# LinearVCA.net
KiCad netlist of a schematic drawn in EAGLE
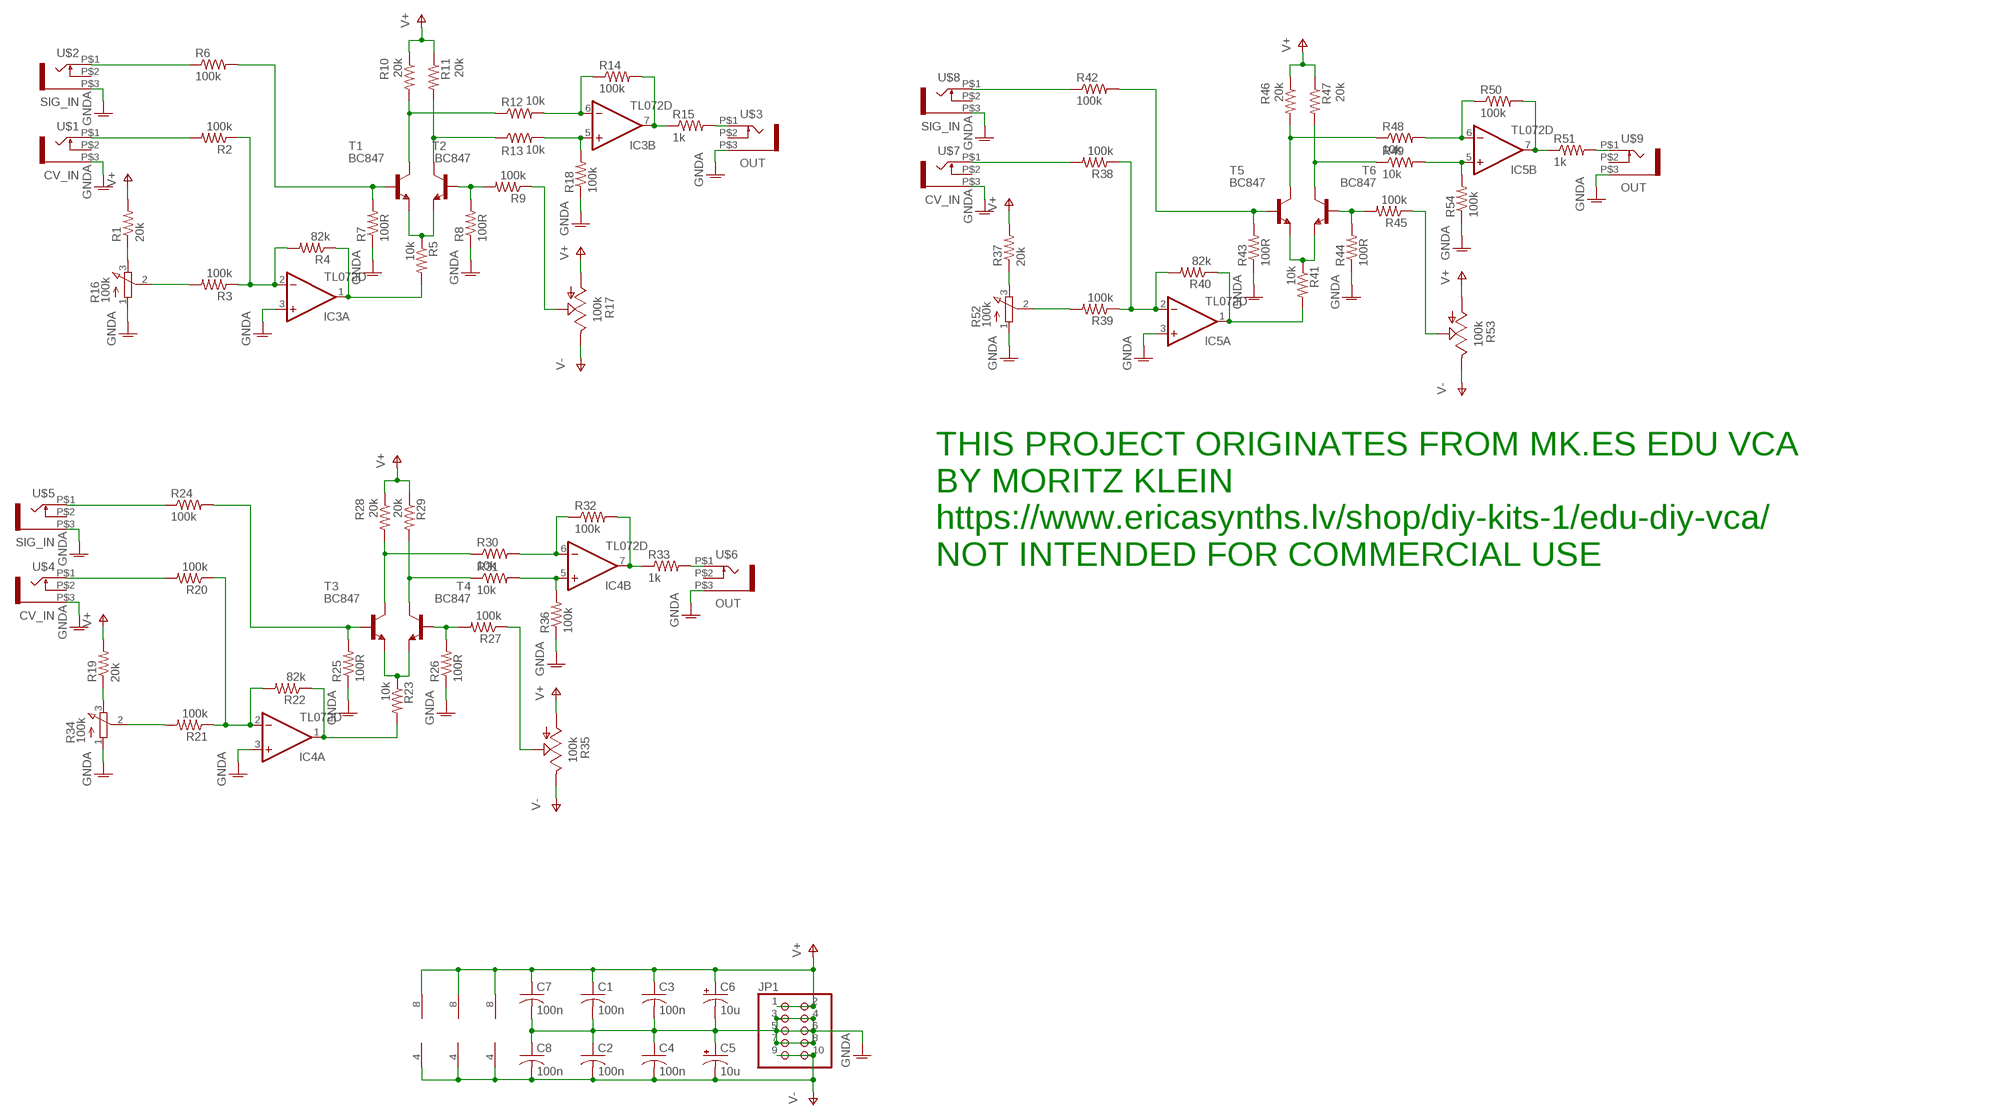
[diagram p0: schematic, sheet 1]

(export (version "E")
  (design (tool "Eeschema 10.0.6"))
  (components
    (comp (ref "C1")
      (value "100n")
      (footprint "eagle-import:C0603K")
      (libsource (lib "eagle-import") (part "C-USC0603K"))
    )
    (comp (ref "C2")
      (value "100n")
      (footprint "eagle-import:C0603K")
      (libsource (lib "eagle-import") (part "C-USC0603K"))
    )
    (comp (ref "C3")
      (value "100n")
      (footprint "eagle-import:C0603K")
      (libsource (lib "eagle-import") (part "C-USC0603K"))
    )
    (comp (ref "C4")
      (value "100n")
      (footprint "eagle-import:C0603K")
      (libsource (lib "eagle-import") (part "C-USC0603K"))
    )
    (comp (ref "C5")
      (value "10u")
      (footprint "eagle-import:E2-5")
      (libsource (lib "eagle-import") (part "CPOL-USE2-5"))
    )
    (comp (ref "C6")
      (value "10u")
      (footprint "eagle-import:E2-5")
      (libsource (lib "eagle-import") (part "CPOL-USE2-5"))
    )
    (comp (ref "C7")
      (value "100n")
      (footprint "eagle-import:C0603K")
      (libsource (lib "eagle-import") (part "C-USC0603K"))
    )
    (comp (ref "C8")
      (value "100n")
      (footprint "eagle-import:C0603K")
      (libsource (lib "eagle-import") (part "C-USC0603K"))
    )
    (comp (ref "IC3")
      (value "TL072D")
      (footprint "eagle-import:SO08")
      (libsource (lib "eagle-import") (part "TL072D"))
    )
    (comp (ref "IC4")
      (value "TL072D")
      (footprint "eagle-import:SO08")
      (libsource (lib "eagle-import") (part "TL072D"))
    )
    (comp (ref "IC5")
      (value "TL072D")
      (footprint "eagle-import:SO08")
      (libsource (lib "eagle-import") (part "TL072D"))
    )
    (comp (ref "JP1")
      (value "PINHD-2X5")
      (footprint "eagle-import:2X05")
      (libsource (lib "eagle-import") (part "PINHD-2X5"))
    )
    (comp (ref "R1")
      (value "20k")
      (footprint "eagle-import:R0603")
      (libsource (lib "eagle-import") (part "R-US_R0603"))
    )
    (comp (ref "R2")
      (value "100k")
      (footprint "eagle-import:R0603")
      (libsource (lib "eagle-import") (part "R-US_R0603"))
    )
    (comp (ref "R3")
      (value "100k")
      (footprint "eagle-import:R0603")
      (libsource (lib "eagle-import") (part "R-US_R0603"))
    )
    (comp (ref "R4")
      (value "82k")
      (footprint "eagle-import:R0603")
      (libsource (lib "eagle-import") (part "R-US_R0603"))
    )
    (comp (ref "R5")
      (value "10k")
      (footprint "eagle-import:R0603")
      (libsource (lib "eagle-import") (part "R-US_R0603"))
    )
    (comp (ref "R6")
      (value "100k")
      (footprint "eagle-import:R0603")
      (libsource (lib "eagle-import") (part "R-US_R0603"))
    )
    (comp (ref "R7")
      (value "100R")
      (footprint "eagle-import:R0603")
      (libsource (lib "eagle-import") (part "R-US_R0603"))
    )
    (comp (ref "R8")
      (value "100R")
      (footprint "eagle-import:R0603")
      (libsource (lib "eagle-import") (part "R-US_R0603"))
    )
    (comp (ref "R9")
      (value "100k")
      (footprint "eagle-import:R0603")
      (libsource (lib "eagle-import") (part "R-US_R0603"))
    )
    (comp (ref "R10")
      (value "20k")
      (footprint "eagle-import:R0603")
      (libsource (lib "eagle-import") (part "R-US_R0603"))
    )
    (comp (ref "R11")
      (value "20k")
      (footprint "eagle-import:R0603")
      (libsource (lib "eagle-import") (part "R-US_R0603"))
    )
    (comp (ref "R12")
      (value "10k")
      (footprint "eagle-import:R0603")
      (libsource (lib "eagle-import") (part "R-US_R0603"))
    )
    (comp (ref "R13")
      (value "10k")
      (footprint "eagle-import:R0603")
      (libsource (lib "eagle-import") (part "R-US_R0603"))
    )
    (comp (ref "R14")
      (value "100k")
      (footprint "eagle-import:R0603")
      (libsource (lib "eagle-import") (part "R-US_R0603"))
    )
    (comp (ref "R15")
      (value "1k")
      (footprint "eagle-import:R0603")
      (libsource (lib "eagle-import") (part "R-US_R0603"))
    )
    (comp (ref "R16")
      (value "100k")
      (footprint "eagle-import:EVUFXK")
      (libsource (lib "eagle-import") (part "EVUF3K"))
    )
    (comp (ref "R17")
      (value "100k")
      (footprint "eagle-import:RJ9W")
      (libsource (lib "eagle-import") (part "TRIM_US-RJ9W"))
    )
    (comp (ref "R18")
      (value "100k")
      (footprint "eagle-import:R0603")
      (libsource (lib "eagle-import") (part "R-US_R0603"))
    )
    (comp (ref "R19")
      (value "20k")
      (footprint "eagle-import:R0603")
      (libsource (lib "eagle-import") (part "R-US_R0603"))
    )
    (comp (ref "R20")
      (value "100k")
      (footprint "eagle-import:R0603")
      (libsource (lib "eagle-import") (part "R-US_R0603"))
    )
    (comp (ref "R21")
      (value "100k")
      (footprint "eagle-import:R0603")
      (libsource (lib "eagle-import") (part "R-US_R0603"))
    )
    (comp (ref "R22")
      (value "82k")
      (footprint "eagle-import:R0603")
      (libsource (lib "eagle-import") (part "R-US_R0603"))
    )
    (comp (ref "R23")
      (value "10k")
      (footprint "eagle-import:R0603")
      (libsource (lib "eagle-import") (part "R-US_R0603"))
    )
    (comp (ref "R24")
      (value "100k")
      (footprint "eagle-import:R0603")
      (libsource (lib "eagle-import") (part "R-US_R0603"))
    )
    (comp (ref "R25")
      (value "100R")
      (footprint "eagle-import:R0603")
      (libsource (lib "eagle-import") (part "R-US_R0603"))
    )
    (comp (ref "R26")
      (value "100R")
      (footprint "eagle-import:R0603")
      (libsource (lib "eagle-import") (part "R-US_R0603"))
    )
    (comp (ref "R27")
      (value "100k")
      (footprint "eagle-import:R0603")
      (libsource (lib "eagle-import") (part "R-US_R0603"))
    )
    (comp (ref "R28")
      (value "20k")
      (footprint "eagle-import:R0603")
      (libsource (lib "eagle-import") (part "R-US_R0603"))
    )
    (comp (ref "R29")
      (value "20k")
      (footprint "eagle-import:R0603")
      (libsource (lib "eagle-import") (part "R-US_R0603"))
    )
    (comp (ref "R30")
      (value "10k")
      (footprint "eagle-import:R0603")
      (libsource (lib "eagle-import") (part "R-US_R0603"))
    )
    (comp (ref "R31")
      (value "10k")
      (footprint "eagle-import:R0603")
      (libsource (lib "eagle-import") (part "R-US_R0603"))
    )
    (comp (ref "R32")
      (value "100k")
      (footprint "eagle-import:R0603")
      (libsource (lib "eagle-import") (part "R-US_R0603"))
    )
    (comp (ref "R33")
      (value "1k")
      (footprint "eagle-import:R0603")
      (libsource (lib "eagle-import") (part "R-US_R0603"))
    )
    (comp (ref "R34")
      (value "100k")
      (footprint "eagle-import:EVUFXK")
      (libsource (lib "eagle-import") (part "EVUF3K"))
    )
    (comp (ref "R35")
      (value "100k")
      (footprint "eagle-import:RJ9W")
      (libsource (lib "eagle-import") (part "TRIM_US-RJ9W"))
    )
    (comp (ref "R36")
      (value "100k")
      (footprint "eagle-import:R0603")
      (libsource (lib "eagle-import") (part "R-US_R0603"))
    )
    (comp (ref "R37")
      (value "20k")
      (footprint "eagle-import:R0603")
      (libsource (lib "eagle-import") (part "R-US_R0603"))
    )
    (comp (ref "R38")
      (value "100k")
      (footprint "eagle-import:R0603")
      (libsource (lib "eagle-import") (part "R-US_R0603"))
    )
    (comp (ref "R39")
      (value "100k")
      (footprint "eagle-import:R0603")
      (libsource (lib "eagle-import") (part "R-US_R0603"))
    )
    (comp (ref "R40")
      (value "82k")
      (footprint "eagle-import:R0603")
      (libsource (lib "eagle-import") (part "R-US_R0603"))
    )
    (comp (ref "R41")
      (value "10k")
      (footprint "eagle-import:R0603")
      (libsource (lib "eagle-import") (part "R-US_R0603"))
    )
    (comp (ref "R42")
      (value "100k")
      (footprint "eagle-import:R0603")
      (libsource (lib "eagle-import") (part "R-US_R0603"))
    )
    (comp (ref "R43")
      (value "100R")
      (footprint "eagle-import:R0603")
      (libsource (lib "eagle-import") (part "R-US_R0603"))
    )
    (comp (ref "R44")
      (value "100R")
      (footprint "eagle-import:R0603")
      (libsource (lib "eagle-import") (part "R-US_R0603"))
    )
    (comp (ref "R45")
      (value "100k")
      (footprint "eagle-import:R0603")
      (libsource (lib "eagle-import") (part "R-US_R0603"))
    )
    (comp (ref "R46")
      (value "20k")
      (footprint "eagle-import:R0603")
      (libsource (lib "eagle-import") (part "R-US_R0603"))
    )
    (comp (ref "R47")
      (value "20k")
      (footprint "eagle-import:R0603")
      (libsource (lib "eagle-import") (part "R-US_R0603"))
    )
    (comp (ref "R48")
      (value "10k")
      (footprint "eagle-import:R0603")
      (libsource (lib "eagle-import") (part "R-US_R0603"))
    )
    (comp (ref "R49")
      (value "10k")
      (footprint "eagle-import:R0603")
      (libsource (lib "eagle-import") (part "R-US_R0603"))
    )
    (comp (ref "R50")
      (value "100k")
      (footprint "eagle-import:R0603")
      (libsource (lib "eagle-import") (part "R-US_R0603"))
    )
    (comp (ref "R51")
      (value "1k")
      (footprint "eagle-import:R0603")
      (libsource (lib "eagle-import") (part "R-US_R0603"))
    )
    (comp (ref "R52")
      (value "100k")
      (footprint "eagle-import:EVUFXK")
      (libsource (lib "eagle-import") (part "EVUF3K"))
    )
    (comp (ref "R53")
      (value "100k")
      (footprint "eagle-import:RJ9W")
      (libsource (lib "eagle-import") (part "TRIM_US-RJ9W"))
    )
    (comp (ref "R54")
      (value "100k")
      (footprint "eagle-import:R0603")
      (libsource (lib "eagle-import") (part "R-US_R0603"))
    )
    (comp (ref "T1")
      (value "BC847")
      (footprint "eagle-import:SOT23")
      (libsource (lib "eagle-import") (part "BC847"))
    )
    (comp (ref "T2")
      (value "BC847")
      (footprint "eagle-import:SOT23")
      (libsource (lib "eagle-import") (part "BC847"))
    )
    (comp (ref "T3")
      (value "BC847")
      (footprint "eagle-import:SOT23")
      (libsource (lib "eagle-import") (part "BC847"))
    )
    (comp (ref "T4")
      (value "BC847")
      (footprint "eagle-import:SOT23")
      (libsource (lib "eagle-import") (part "BC847"))
    )
    (comp (ref "T5")
      (value "BC847")
      (footprint "eagle-import:SOT23")
      (libsource (lib "eagle-import") (part "BC847"))
    )
    (comp (ref "T6")
      (value "BC847")
      (footprint "eagle-import:SOT23")
      (libsource (lib "eagle-import") (part "BC847"))
    )
    (comp (ref "U$1")
      (value "CV_IN")
      (footprint "eagle-import:WQP-PJ301M-12_JACK")
      (libsource (lib "eagle-import") (part "WQP-PJ301M-12_JACK"))
    )
    (comp (ref "U$2")
      (value "SIG_IN")
      (footprint "eagle-import:WQP-PJ301M-12_JACK")
      (libsource (lib "eagle-import") (part "WQP-PJ301M-12_JACK"))
    )
    (comp (ref "U$3")
      (value "OUT")
      (footprint "eagle-import:WQP-PJ301M-12_JACK")
      (libsource (lib "eagle-import") (part "WQP-PJ301M-12_JACK"))
    )
    (comp (ref "U$4")
      (value "CV_IN")
      (footprint "eagle-import:WQP-PJ301M-12_JACK")
      (libsource (lib "eagle-import") (part "WQP-PJ301M-12_JACK"))
    )
    (comp (ref "U$5")
      (value "SIG_IN")
      (footprint "eagle-import:WQP-PJ301M-12_JACK")
      (libsource (lib "eagle-import") (part "WQP-PJ301M-12_JACK"))
    )
    (comp (ref "U$6")
      (value "OUT")
      (footprint "eagle-import:WQP-PJ301M-12_JACK")
      (libsource (lib "eagle-import") (part "WQP-PJ301M-12_JACK"))
    )
    (comp (ref "U$7")
      (value "CV_IN")
      (footprint "eagle-import:WQP-PJ301M-12_JACK")
      (libsource (lib "eagle-import") (part "WQP-PJ301M-12_JACK"))
    )
    (comp (ref "U$8")
      (value "SIG_IN")
      (footprint "eagle-import:WQP-PJ301M-12_JACK")
      (libsource (lib "eagle-import") (part "WQP-PJ301M-12_JACK"))
    )
    (comp (ref "U$9")
      (value "OUT")
      (footprint "eagle-import:WQP-PJ301M-12_JACK")
      (libsource (lib "eagle-import") (part "WQP-PJ301M-12_JACK"))
    )
  )
  (nets
    (net (code "1") (name "GNDA") (class "Default")
      (node (ref "C1") (pin "2") (pinfunction "2_2") (pintype "passive"))
      (node (ref "C2") (pin "1") (pinfunction "1_1") (pintype "passive"))
      (node (ref "C3") (pin "2") (pinfunction "2_2") (pintype "passive"))
      (node (ref "C4") (pin "1") (pinfunction "1_1") (pintype "passive"))
      (node (ref "C5") (pin "+") (pinfunction "+_+") (pintype "passive"))
      (node (ref "C6") (pin "-") (pinfunction "-_-") (pintype "passive"))
      (node (ref "C7") (pin "2") (pinfunction "2_2") (pintype "passive"))
      (node (ref "C8") (pin "1") (pinfunction "1_1") (pintype "passive"))
      (node (ref "IC3") (pin "3") (pinfunction "+IN_3") (pintype "input"))
      (node (ref "IC4") (pin "3") (pinfunction "+IN_3") (pintype "input"))
      (node (ref "IC5") (pin "3") (pinfunction "+IN_3") (pintype "input"))
      (node (ref "JP1") (pin "3") (pinfunction "3_3") (pintype "passive"))
      (node (ref "JP1") (pin "4") (pinfunction "4_4") (pintype "passive"))
      (node (ref "JP1") (pin "5") (pinfunction "5_5") (pintype "passive"))
      (node (ref "JP1") (pin "6") (pinfunction "6_6") (pintype "passive"))
      (node (ref "JP1") (pin "7") (pinfunction "7_7") (pintype "passive"))
      (node (ref "JP1") (pin "8") (pinfunction "8_8") (pintype "passive"))
      (node (ref "R16") (pin "1") (pinfunction "A_1") (pintype "passive"))
      (node (ref "R18") (pin "1") (pinfunction "1_1") (pintype "passive"))
      (node (ref "R25") (pin "1") (pinfunction "1_1") (pintype "passive"))
      (node (ref "R26") (pin "1") (pinfunction "1_1") (pintype "passive"))
      (node (ref "R34") (pin "1") (pinfunction "A_1") (pintype "passive"))
      (node (ref "R36") (pin "1") (pinfunction "1_1") (pintype "passive"))
      (node (ref "R43") (pin "1") (pinfunction "1_1") (pintype "passive"))
      (node (ref "R44") (pin "1") (pinfunction "1_1") (pintype "passive"))
      (node (ref "R52") (pin "1") (pinfunction "A_1") (pintype "passive"))
      (node (ref "R54") (pin "1") (pinfunction "1_1") (pintype "passive"))
      (node (ref "R7") (pin "1") (pinfunction "1_1") (pintype "passive"))
      (node (ref "R8") (pin "1") (pinfunction "1_1") (pintype "passive"))
      (node (ref "U$1") (pin "P$3") (pinfunction "1_P$3") (pintype "passive"))
      (node (ref "U$2") (pin "P$3") (pinfunction "1_P$3") (pintype "passive"))
      (node (ref "U$3") (pin "P$3") (pinfunction "1_P$3") (pintype "passive"))
      (node (ref "U$4") (pin "P$3") (pinfunction "1_P$3") (pintype "passive"))
      (node (ref "U$5") (pin "P$3") (pinfunction "1_P$3") (pintype "passive"))
      (node (ref "U$6") (pin "P$3") (pinfunction "1_P$3") (pintype "passive"))
      (node (ref "U$7") (pin "P$3") (pinfunction "1_P$3") (pintype "passive"))
      (node (ref "U$8") (pin "P$3") (pinfunction "1_P$3") (pintype "passive"))
      (node (ref "U$9") (pin "P$3") (pinfunction "1_P$3") (pintype "passive"))
    )
    (net (code "2") (name "Net-(IC3A--IN)") (class "Default")
      (node (ref "IC3") (pin "2") (pinfunction "-IN_2") (pintype "input"))
      (node (ref "R2") (pin "1") (pinfunction "1_1") (pintype "passive"))
      (node (ref "R3") (pin "1") (pinfunction "1_1") (pintype "passive"))
      (node (ref "R4") (pin "2") (pinfunction "2_2") (pintype "passive"))
    )
    (net (code "3") (name "Net-(IC3A-OUT)") (class "Default")
      (node (ref "IC3") (pin "1") (pinfunction "OUT_1") (pintype "output"))
      (node (ref "R4") (pin "1") (pinfunction "1_1") (pintype "passive"))
      (node (ref "R5") (pin "2") (pinfunction "2_2") (pintype "passive"))
    )
    (net (code "4") (name "Net-(IC3B-+IN)") (class "Default")
      (node (ref "IC3") (pin "5") (pinfunction "+IN_5") (pintype "input"))
      (node (ref "R13") (pin "2") (pinfunction "2_2") (pintype "passive"))
      (node (ref "R18") (pin "2") (pinfunction "2_2") (pintype "passive"))
    )
    (net (code "5") (name "Net-(IC3B--IN)") (class "Default")
      (node (ref "IC3") (pin "6") (pinfunction "-IN_6") (pintype "input"))
      (node (ref "R12") (pin "2") (pinfunction "2_2") (pintype "passive"))
      (node (ref "R14") (pin "1") (pinfunction "1_1") (pintype "passive"))
    )
    (net (code "6") (name "Net-(IC3B-OUT)") (class "Default")
      (node (ref "IC3") (pin "7") (pinfunction "OUT_7") (pintype "output"))
      (node (ref "R14") (pin "2") (pinfunction "2_2") (pintype "passive"))
      (node (ref "R15") (pin "1") (pinfunction "1_1") (pintype "passive"))
    )
    (net (code "7") (name "Net-(IC4A--IN)") (class "Default")
      (node (ref "IC4") (pin "2") (pinfunction "-IN_2") (pintype "input"))
      (node (ref "R20") (pin "1") (pinfunction "1_1") (pintype "passive"))
      (node (ref "R21") (pin "1") (pinfunction "1_1") (pintype "passive"))
      (node (ref "R22") (pin "2") (pinfunction "2_2") (pintype "passive"))
    )
    (net (code "8") (name "Net-(IC4A-OUT)") (class "Default")
      (node (ref "IC4") (pin "1") (pinfunction "OUT_1") (pintype "output"))
      (node (ref "R22") (pin "1") (pinfunction "1_1") (pintype "passive"))
      (node (ref "R23") (pin "2") (pinfunction "2_2") (pintype "passive"))
    )
    (net (code "9") (name "Net-(IC4B-+IN)") (class "Default")
      (node (ref "IC4") (pin "5") (pinfunction "+IN_5") (pintype "input"))
      (node (ref "R31") (pin "2") (pinfunction "2_2") (pintype "passive"))
      (node (ref "R36") (pin "2") (pinfunction "2_2") (pintype "passive"))
    )
    (net (code "10") (name "Net-(IC4B--IN)") (class "Default")
      (node (ref "IC4") (pin "6") (pinfunction "-IN_6") (pintype "input"))
      (node (ref "R30") (pin "2") (pinfunction "2_2") (pintype "passive"))
      (node (ref "R32") (pin "1") (pinfunction "1_1") (pintype "passive"))
    )
    (net (code "11") (name "Net-(IC4B-OUT)") (class "Default")
      (node (ref "IC4") (pin "7") (pinfunction "OUT_7") (pintype "output"))
      (node (ref "R32") (pin "2") (pinfunction "2_2") (pintype "passive"))
      (node (ref "R33") (pin "1") (pinfunction "1_1") (pintype "passive"))
    )
    (net (code "12") (name "Net-(IC5A--IN)") (class "Default")
      (node (ref "IC5") (pin "2") (pinfunction "-IN_2") (pintype "input"))
      (node (ref "R38") (pin "1") (pinfunction "1_1") (pintype "passive"))
      (node (ref "R39") (pin "1") (pinfunction "1_1") (pintype "passive"))
      (node (ref "R40") (pin "2") (pinfunction "2_2") (pintype "passive"))
    )
    (net (code "13") (name "Net-(IC5A-OUT)") (class "Default")
      (node (ref "IC5") (pin "1") (pinfunction "OUT_1") (pintype "output"))
      (node (ref "R40") (pin "1") (pinfunction "1_1") (pintype "passive"))
      (node (ref "R41") (pin "2") (pinfunction "2_2") (pintype "passive"))
    )
    (net (code "14") (name "Net-(IC5B-+IN)") (class "Default")
      (node (ref "IC5") (pin "5") (pinfunction "+IN_5") (pintype "input"))
      (node (ref "R49") (pin "2") (pinfunction "2_2") (pintype "passive"))
      (node (ref "R54") (pin "2") (pinfunction "2_2") (pintype "passive"))
    )
    (net (code "15") (name "Net-(IC5B--IN)") (class "Default")
      (node (ref "IC5") (pin "6") (pinfunction "-IN_6") (pintype "input"))
      (node (ref "R48") (pin "2") (pinfunction "2_2") (pintype "passive"))
      (node (ref "R50") (pin "1") (pinfunction "1_1") (pintype "passive"))
    )
    (net (code "16") (name "Net-(IC5B-OUT)") (class "Default")
      (node (ref "IC5") (pin "7") (pinfunction "OUT_7") (pintype "output"))
      (node (ref "R50") (pin "2") (pinfunction "2_2") (pintype "passive"))
      (node (ref "R51") (pin "1") (pinfunction "1_1") (pintype "passive"))
    )
    (net (code "17") (name "Net-(R16-E)") (class "Default")
      (node (ref "R1") (pin "1") (pinfunction "1_1") (pintype "passive"))
      (node (ref "R16") (pin "3") (pinfunction "E_3") (pintype "passive"))
    )
    (net (code "18") (name "Net-(R16-S)") (class "Default")
      (node (ref "R16") (pin "2") (pinfunction "S_2") (pintype "passive"))
      (node (ref "R3") (pin "2") (pinfunction "2_2") (pintype "passive"))
    )
    (net (code "19") (name "Net-(R17-PadS)") (class "Default")
      (node (ref "R17") (pin "S") (pinfunction "S_S") (pintype "passive"))
      (node (ref "R9") (pin "1") (pinfunction "1_1") (pintype "passive"))
    )
    (net (code "20") (name "Net-(R27-Pad1)") (class "Default")
      (node (ref "R27") (pin "1") (pinfunction "1_1") (pintype "passive"))
      (node (ref "R35") (pin "S") (pinfunction "S_S") (pintype "passive"))
    )
    (net (code "21") (name "Net-(R34-E)") (class "Default")
      (node (ref "R19") (pin "1") (pinfunction "1_1") (pintype "passive"))
      (node (ref "R34") (pin "3") (pinfunction "E_3") (pintype "passive"))
    )
    (net (code "22") (name "Net-(R34-S)") (class "Default")
      (node (ref "R21") (pin "2") (pinfunction "2_2") (pintype "passive"))
      (node (ref "R34") (pin "2") (pinfunction "S_2") (pintype "passive"))
    )
    (net (code "23") (name "Net-(R45-Pad1)") (class "Default")
      (node (ref "R45") (pin "1") (pinfunction "1_1") (pintype "passive"))
      (node (ref "R53") (pin "S") (pinfunction "S_S") (pintype "passive"))
    )
    (net (code "24") (name "Net-(R52-E)") (class "Default")
      (node (ref "R37") (pin "1") (pinfunction "1_1") (pintype "passive"))
      (node (ref "R52") (pin "3") (pinfunction "E_3") (pintype "passive"))
    )
    (net (code "25") (name "Net-(R52-S)") (class "Default")
      (node (ref "R39") (pin "2") (pinfunction "2_2") (pintype "passive"))
      (node (ref "R52") (pin "2") (pinfunction "S_2") (pintype "passive"))
    )
    (net (code "26") (name "Net-(T1-B)") (class "Default")
      (node (ref "R6") (pin "2") (pinfunction "2_2") (pintype "passive"))
      (node (ref "R7") (pin "2") (pinfunction "2_2") (pintype "passive"))
      (node (ref "T1") (pin "1") (pinfunction "B_1") (pintype "passive"))
    )
    (net (code "27") (name "Net-(T1-C)") (class "Default")
      (node (ref "R10") (pin "2") (pinfunction "2_2") (pintype "passive"))
      (node (ref "R12") (pin "1") (pinfunction "1_1") (pintype "passive"))
      (node (ref "T1") (pin "3") (pinfunction "C_3") (pintype "passive"))
    )
    (net (code "28") (name "Net-(T1-E)") (class "Default")
      (node (ref "R5") (pin "1") (pinfunction "1_1") (pintype "passive"))
      (node (ref "T1") (pin "2") (pinfunction "E_2") (pintype "passive"))
      (node (ref "T2") (pin "2") (pinfunction "E_2") (pintype "passive"))
    )
    (net (code "29") (name "Net-(T2-B)") (class "Default")
      (node (ref "R8") (pin "2") (pinfunction "2_2") (pintype "passive"))
      (node (ref "R9") (pin "2") (pinfunction "2_2") (pintype "passive"))
      (node (ref "T2") (pin "1") (pinfunction "B_1") (pintype "passive"))
    )
    (net (code "30") (name "Net-(T2-C)") (class "Default")
      (node (ref "R11") (pin "2") (pinfunction "2_2") (pintype "passive"))
      (node (ref "R13") (pin "1") (pinfunction "1_1") (pintype "passive"))
      (node (ref "T2") (pin "3") (pinfunction "C_3") (pintype "passive"))
    )
    (net (code "31") (name "Net-(T3-B)") (class "Default")
      (node (ref "R24") (pin "2") (pinfunction "2_2") (pintype "passive"))
      (node (ref "R25") (pin "2") (pinfunction "2_2") (pintype "passive"))
      (node (ref "T3") (pin "1") (pinfunction "B_1") (pintype "passive"))
    )
    (net (code "32") (name "Net-(T3-C)") (class "Default")
      (node (ref "R28") (pin "2") (pinfunction "2_2") (pintype "passive"))
      (node (ref "R30") (pin "1") (pinfunction "1_1") (pintype "passive"))
      (node (ref "T3") (pin "3") (pinfunction "C_3") (pintype "passive"))
    )
    (net (code "33") (name "Net-(T3-E)") (class "Default")
      (node (ref "R23") (pin "1") (pinfunction "1_1") (pintype "passive"))
      (node (ref "T3") (pin "2") (pinfunction "E_2") (pintype "passive"))
      (node (ref "T4") (pin "2") (pinfunction "E_2") (pintype "passive"))
    )
    (net (code "34") (name "Net-(T4-B)") (class "Default")
      (node (ref "R26") (pin "2") (pinfunction "2_2") (pintype "passive"))
      (node (ref "R27") (pin "2") (pinfunction "2_2") (pintype "passive"))
      (node (ref "T4") (pin "1") (pinfunction "B_1") (pintype "passive"))
    )
    (net (code "35") (name "Net-(T4-C)") (class "Default")
      (node (ref "R29") (pin "2") (pinfunction "2_2") (pintype "passive"))
      (node (ref "R31") (pin "1") (pinfunction "1_1") (pintype "passive"))
      (node (ref "T4") (pin "3") (pinfunction "C_3") (pintype "passive"))
    )
    (net (code "36") (name "Net-(T5-B)") (class "Default")
      (node (ref "R42") (pin "2") (pinfunction "2_2") (pintype "passive"))
      (node (ref "R43") (pin "2") (pinfunction "2_2") (pintype "passive"))
      (node (ref "T5") (pin "1") (pinfunction "B_1") (pintype "passive"))
    )
    (net (code "37") (name "Net-(T5-C)") (class "Default")
      (node (ref "R46") (pin "2") (pinfunction "2_2") (pintype "passive"))
      (node (ref "R48") (pin "1") (pinfunction "1_1") (pintype "passive"))
      (node (ref "T5") (pin "3") (pinfunction "C_3") (pintype "passive"))
    )
    (net (code "38") (name "Net-(T5-E)") (class "Default")
      (node (ref "R41") (pin "1") (pinfunction "1_1") (pintype "passive"))
      (node (ref "T5") (pin "2") (pinfunction "E_2") (pintype "passive"))
      (node (ref "T6") (pin "2") (pinfunction "E_2") (pintype "passive"))
    )
    (net (code "39") (name "Net-(T6-B)") (class "Default")
      (node (ref "R44") (pin "2") (pinfunction "2_2") (pintype "passive"))
      (node (ref "R45") (pin "2") (pinfunction "2_2") (pintype "passive"))
      (node (ref "T6") (pin "1") (pinfunction "B_1") (pintype "passive"))
    )
    (net (code "40") (name "Net-(T6-C)") (class "Default")
      (node (ref "R47") (pin "2") (pinfunction "2_2") (pintype "passive"))
      (node (ref "R49") (pin "1") (pinfunction "1_1") (pintype "passive"))
      (node (ref "T6") (pin "3") (pinfunction "C_3") (pintype "passive"))
    )
    (net (code "41") (name "Net-(U$1-2)") (class "Default")
      (node (ref "R2") (pin "2") (pinfunction "2_2") (pintype "passive"))
      (node (ref "U$1") (pin "P$1") (pinfunction "2_P$1") (pintype "passive"))
    )
    (net (code "42") (name "Net-(U$2-2)") (class "Default")
      (node (ref "R6") (pin "1") (pinfunction "1_1") (pintype "passive"))
      (node (ref "U$2") (pin "P$1") (pinfunction "2_P$1") (pintype "passive"))
    )
    (net (code "43") (name "Net-(U$3-2)") (class "Default")
      (node (ref "R15") (pin "2") (pinfunction "2_2") (pintype "passive"))
      (node (ref "U$3") (pin "P$1") (pinfunction "2_P$1") (pintype "passive"))
    )
    (net (code "44") (name "Net-(U$4-2)") (class "Default")
      (node (ref "R20") (pin "2") (pinfunction "2_2") (pintype "passive"))
      (node (ref "U$4") (pin "P$1") (pinfunction "2_P$1") (pintype "passive"))
    )
    (net (code "45") (name "Net-(U$5-2)") (class "Default")
      (node (ref "R24") (pin "1") (pinfunction "1_1") (pintype "passive"))
      (node (ref "U$5") (pin "P$1") (pinfunction "2_P$1") (pintype "passive"))
    )
    (net (code "46") (name "Net-(U$6-2)") (class "Default")
      (node (ref "R33") (pin "2") (pinfunction "2_2") (pintype "passive"))
      (node (ref "U$6") (pin "P$1") (pinfunction "2_P$1") (pintype "passive"))
    )
    (net (code "47") (name "Net-(U$7-2)") (class "Default")
      (node (ref "R38") (pin "2") (pinfunction "2_2") (pintype "passive"))
      (node (ref "U$7") (pin "P$1") (pinfunction "2_P$1") (pintype "passive"))
    )
    (net (code "48") (name "Net-(U$8-2)") (class "Default")
      (node (ref "R42") (pin "1") (pinfunction "1_1") (pintype "passive"))
      (node (ref "U$8") (pin "P$1") (pinfunction "2_P$1") (pintype "passive"))
    )
    (net (code "49") (name "Net-(U$9-2)") (class "Default")
      (node (ref "R51") (pin "2") (pinfunction "2_2") (pintype "passive"))
      (node (ref "U$9") (pin "P$1") (pinfunction "2_P$1") (pintype "passive"))
    )
    (net (code "50") (name "V+") (class "Default")
      (node (ref "C1") (pin "1") (pinfunction "1_1") (pintype "passive"))
      (node (ref "C3") (pin "1") (pinfunction "1_1") (pintype "passive"))
      (node (ref "C6") (pin "+") (pinfunction "+_+") (pintype "passive"))
      (node (ref "C7") (pin "1") (pinfunction "1_1") (pintype "passive"))
      (node (ref "IC3") (pin "8") (pinfunction "V+_8") (pintype "power_in"))
      (node (ref "IC4") (pin "8") (pinfunction "V+_8") (pintype "power_in"))
      (node (ref "IC5") (pin "8") (pinfunction "V+_8") (pintype "power_in"))
      (node (ref "JP1") (pin "1") (pinfunction "1_1") (pintype "passive"))
      (node (ref "JP1") (pin "2") (pinfunction "2_2") (pintype "passive"))
      (node (ref "R1") (pin "2") (pinfunction "2_2") (pintype "passive"))
      (node (ref "R10") (pin "1") (pinfunction "1_1") (pintype "passive"))
      (node (ref "R11") (pin "1") (pinfunction "1_1") (pintype "passive"))
      (node (ref "R17") (pin "A") (pinfunction "A_A") (pintype "passive"))
      (node (ref "R19") (pin "2") (pinfunction "2_2") (pintype "passive"))
      (node (ref "R28") (pin "1") (pinfunction "1_1") (pintype "passive"))
      (node (ref "R29") (pin "1") (pinfunction "1_1") (pintype "passive"))
      (node (ref "R35") (pin "A") (pinfunction "A_A") (pintype "passive"))
      (node (ref "R37") (pin "2") (pinfunction "2_2") (pintype "passive"))
      (node (ref "R46") (pin "1") (pinfunction "1_1") (pintype "passive"))
      (node (ref "R47") (pin "1") (pinfunction "1_1") (pintype "passive"))
      (node (ref "R53") (pin "A") (pinfunction "A_A") (pintype "passive"))
    )
    (net (code "51") (name "V-") (class "Default")
      (node (ref "C2") (pin "2") (pinfunction "2_2") (pintype "passive"))
      (node (ref "C4") (pin "2") (pinfunction "2_2") (pintype "passive"))
      (node (ref "C5") (pin "-") (pinfunction "-_-") (pintype "passive"))
      (node (ref "C8") (pin "2") (pinfunction "2_2") (pintype "passive"))
      (node (ref "IC3") (pin "4") (pinfunction "V-_4") (pintype "power_in"))
      (node (ref "IC4") (pin "4") (pinfunction "V-_4") (pintype "power_in"))
      (node (ref "IC5") (pin "4") (pinfunction "V-_4") (pintype "power_in"))
      (node (ref "JP1") (pin "10") (pinfunction "10_10") (pintype "passive"))
      (node (ref "JP1") (pin "9") (pinfunction "9_9") (pintype "passive"))
      (node (ref "R17") (pin "E") (pinfunction "E_E") (pintype "passive"))
      (node (ref "R35") (pin "E") (pinfunction "E_E") (pintype "passive"))
      (node (ref "R53") (pin "E") (pinfunction "E_E") (pintype "passive"))
    )
    (net (code "52") (name "unconnected-(U$1-3-PadP$2)") (class "Default")
      (node (ref "U$1") (pin "P$2") (pinfunction "3_P$2") (pintype "passive"))
    )
    (net (code "53") (name "unconnected-(U$2-3-PadP$2)") (class "Default")
      (node (ref "U$2") (pin "P$2") (pinfunction "3_P$2") (pintype "passive"))
    )
    (net (code "54") (name "unconnected-(U$3-3-PadP$2)") (class "Default")
      (node (ref "U$3") (pin "P$2") (pinfunction "3_P$2") (pintype "passive"))
    )
    (net (code "55") (name "unconnected-(U$4-3-PadP$2)") (class "Default")
      (node (ref "U$4") (pin "P$2") (pinfunction "3_P$2") (pintype "passive"))
    )
    (net (code "56") (name "unconnected-(U$5-3-PadP$2)") (class "Default")
      (node (ref "U$5") (pin "P$2") (pinfunction "3_P$2") (pintype "passive"))
    )
    (net (code "57") (name "unconnected-(U$6-3-PadP$2)") (class "Default")
      (node (ref "U$6") (pin "P$2") (pinfunction "3_P$2") (pintype "passive"))
    )
    (net (code "58") (name "unconnected-(U$7-3-PadP$2)") (class "Default")
      (node (ref "U$7") (pin "P$2") (pinfunction "3_P$2") (pintype "passive"))
    )
    (net (code "59") (name "unconnected-(U$8-3-PadP$2)") (class "Default")
      (node (ref "U$8") (pin "P$2") (pinfunction "3_P$2") (pintype "passive"))
    )
    (net (code "60") (name "unconnected-(U$9-3-PadP$2)") (class "Default")
      (node (ref "U$9") (pin "P$2") (pinfunction "3_P$2") (pintype "passive"))
    )
  )
)
